# Sheet1.net
KiCad netlist of a schematic drawn in Altium Designer
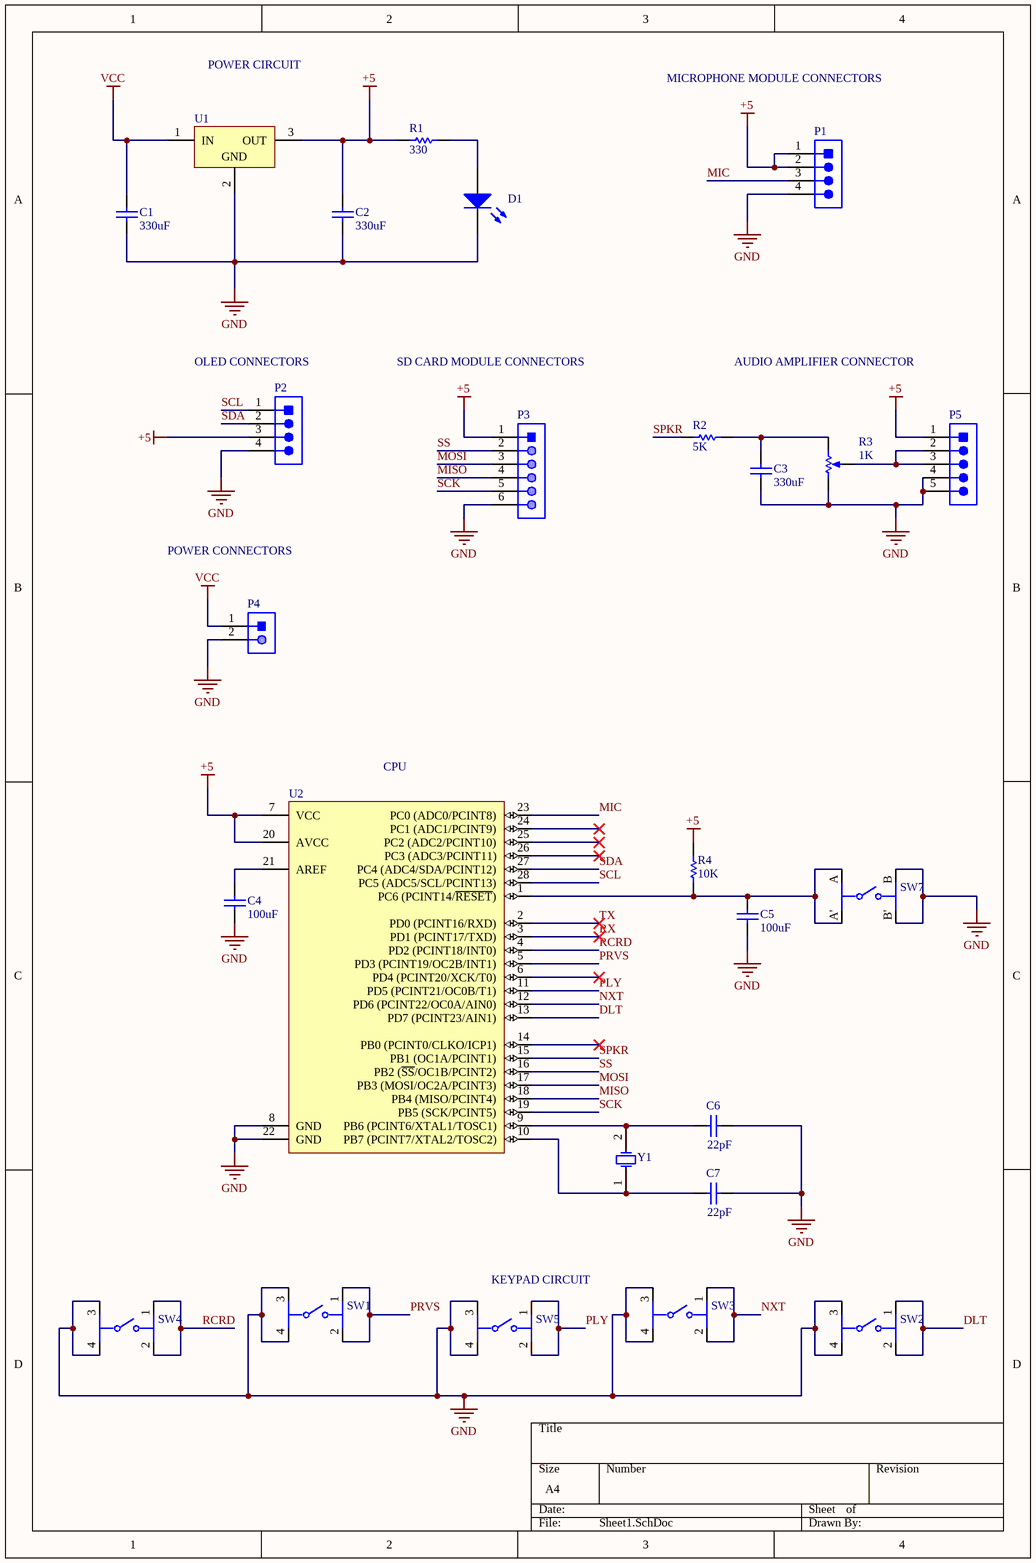
[diagram p0: Sheet1.SchDoc]

(export (version "E")
  (design (tool "Eeschema 10.0.6"))
  (components
    (comp (ref "C1")
      (value "330uF")
      (footprint "RAD-0.3")
      (description "Capacitor")
      (fields (field (name "PUBLISHER") "Altium Limited"))
      (libsource (lib "Miscellaneous Devices") (part "Cap"))
    )
    (comp (ref "C2")
      (value "330uF")
      (footprint "RAD-0.3")
      (description "Capacitor")
      (fields (field (name "PUBLISHER") "Altium Limited"))
      (libsource (lib "Miscellaneous Devices") (part "Cap"))
    )
    (comp (ref "C3")
      (value "330uF")
      (footprint "RAD-0.3")
      (description "Capacitor")
      (fields (field (name "PUBLISHER") "Altium Limited"))
      (libsource (lib "Miscellaneous Devices") (part "Cap"))
    )
    (comp (ref "C4")
      (value "~")
      (footprint "KEMT-C330C105M5U5TA")
      (description "Ceramic Capacitor, 1 uF, +/- 20%, 50 V, -10 to 85 degC, 2-Pin THD, RoHS, Bulk")
      (fields
        (field (name "TOLERANCE") "±20%")
        (field (name "CAPACITANCE") "100uF")
        (field (name "MANUFACTURER") "Kemet")
      )
      (libsource (lib "Altium Content Vault") (part "CAP-NP-2"))
    )
    (comp (ref "C5")
      (value "C330C105M5U5TA")
      (footprint "KEMT-C330C105M5U5TA")
      (description "Ceramic Capacitor, 1 uF, +/- 20%, 50 V, -10 to 85 degC, 2-Pin THD, RoHS, Bulk")
      (fields
        (field (name "TOLERANCE") "±20%")
        (field (name "CAPACITANCE") "100uF")
        (field (name "MANUFACTURER") "Kemet")
      )
      (libsource (lib "Altium Content Vault") (part "CAP-NP-2"))
    )
    (comp (ref "C6")
      (value "C330C105M5U5TA")
      (footprint "KEMT-C330C105M5U5TA")
      (description "Ceramic Capacitor, 1 uF, +/- 20%, 50 V, -10 to 85 degC, 2-Pin THD, RoHS, Bulk")
      (fields
        (field (name "TOLERANCE") "±20%")
        (field (name "CAPACITANCE") "22pF")
        (field (name "MANUFACTURER") "Kemet")
      )
      (libsource (lib "Altium Content Vault") (part "CAP-NP-2"))
    )
    (comp (ref "C7")
      (value "C330C105M5U5TA")
      (footprint "KEMT-C330C105M5U5TA")
      (description "Ceramic Capacitor, 1 uF, +/- 20%, 50 V, -10 to 85 degC, 2-Pin THD, RoHS, Bulk")
      (fields
        (field (name "TOLERANCE") "±20%")
        (field (name "CAPACITANCE") "22pF")
        (field (name "MANUFACTURER") "Kemet")
      )
      (libsource (lib "Altium Content Vault") (part "CAP-NP-2"))
    )
    (comp (ref "D1")
      (value "LED1")
      (footprint "LED-1")
      (description "Typical RED GaAs LED")
      (fields (field (name "PUBLISHER") "Altium Limited"))
      (libsource (lib "Miscellaneous Devices") (part "LED1"))
    )
    (comp (ref "P1")
      (value "640456-4")
      (footprint "TECO-640456-4")
      (description "Male Header, Pitch 2.54 mm, 1 x 4 Position, Height 10.03 mm, Tail Length 3.56 mm, RoHS, Bulk")
      (fields (field (name "MANUFACTURER") "TE Connectivity"))
      (libsource (lib "Altium Content Vault") (part "CN-1P-M-R4"))
    )
    (comp (ref "P2")
      (value "640456-4")
      (footprint "TECO-640456-4")
      (description "Male Header, Pitch 2.54 mm, 1 x 4 Position, Height 10.03 mm, Tail Length 3.56 mm, RoHS, Bulk")
      (fields (field (name "MANUFACTURER") "TE Connectivity"))
      (libsource (lib "Altium Content Vault") (part "CN-1P-M-R4"))
    )
    (comp (ref "P3")
      (value "66200611122")
      (footprint "66200611122")
      (description "THT Male Header WR-MPC3, Vertical, Single Row, pitch 3 mm, 6 pins")
      (fields (field (name "MANUFACTURER") "Wurth Elektronik") (field (name "PUBLISHER") "WurthElektronik"))
      (libsource (lib "Altium Content Vault") (part "WE-CN-1P-M-R6"))
    )
    (comp (ref "P4")
      (value "61900211121")
      (footprint "61900211121")
      (description "Male Locking Header WR-WTB, THT, Vertical, pitch 2.54 mm, 1 x 2 position")
      (fields (field (name "MANUFACTURER") "Wurth Elektronik") (field (name "PUBLISHER") "WurthElektronik"))
      (libsource (lib "Altium Content Vault") (part "WE-CN-1P-M-R2"))
    )
    (comp (ref "P5")
      (value "640456-5")
      (footprint "TECO-640456-5")
      (fields (field (name "MANUFACTURER") "TE Connectivity"))
      (libsource (lib "Altium Content Vault") (part "CN-1P-M-R5"))
    )
    (comp (ref "R1")
      (value "330")
      (footprint "AXIAL-0.3")
      (description "Resistor")
      (fields (field (name "PUBLISHER") "Altium Limited"))
      (libsource (lib "Miscellaneous Devices") (part "Res1"))
    )
    (comp (ref "R2")
      (value "5K")
      (footprint "AXIAL-0.3")
      (description "Resistor")
      (fields (field (name "PUBLISHER") "Altium Limited"))
      (libsource (lib "Miscellaneous Devices") (part "Res1"))
    )
    (comp (ref "R3")
      (value "1K")
      (footprint "VR5")
      (description "Potentiometer")
      (fields (field (name "PUBLISHER") "Altium Limited"))
      (libsource (lib "Miscellaneous Devices") (part "RPot"))
    )
    (comp (ref "R4")
      (value "10K")
      (footprint "AXIAL-0.3")
      (description "Resistor")
      (fields (field (name "PUBLISHER") "Altium Limited"))
      (libsource (lib "Miscellaneous Devices") (part "Res1"))
    )
    (comp (ref "SW1")
      (value "FSM100")
      (footprint "FP-FSM100-MFG")
      (description "SWITCH TACTILE SPST-NO 0.05A 24V")
      (libsource (lib "Altium Content Vault") (part "1adf0dd01260c80cf25a44bfd6b99ba"))
    )
    (comp (ref "SW2")
      (value "FSM100")
      (footprint "FP-FSM100-MFG")
      (description "SWITCH TACTILE SPST-NO 0.05A 24V")
      (libsource (lib "Altium Content Vault") (part "1adf0dd01260c80cf25a44bfd6b99ba"))
    )
    (comp (ref "SW3")
      (value "FSM100")
      (footprint "FP-FSM100-MFG")
      (description "SWITCH TACTILE SPST-NO 0.05A 24V")
      (libsource (lib "Altium Content Vault") (part "1adf0dd01260c80cf25a44bfd6b99ba"))
    )
    (comp (ref "SW4")
      (value "FSM100")
      (footprint "FP-FSM100-MFG")
      (description "SWITCH TACTILE SPST-NO 0.05A 24V")
      (libsource (lib "Altium Content Vault") (part "1adf0dd01260c80cf25a44bfd6b99ba"))
    )
    (comp (ref "SW5")
      (value "FSM100")
      (footprint "FP-FSM100-MFG")
      (description "SWITCH TACTILE SPST-NO 0.05A 24V")
      (libsource (lib "Altium Content Vault") (part "1adf0dd01260c80cf25a44bfd6b99ba"))
    )
    (comp (ref "SW7")
      (value "EVQ-PAG07K")
      (footprint "FP-EVQ-PAG07K-MFG")
      (description "SWITCH TACTILE SPST-NO 0.02A 15V")
      (libsource (lib "Altium Content Vault") (part "75038bc65b1af1a6bd057da08483287"))
    )
    (comp (ref "U1")
      (value "L7805CV")
      (footprint "TO220")
      (description "Positive Voltage Regulator, 5V, 3-Pin TO-220")
      (libsource (lib "Altium Content Vault") (part "PM-REG-L4940-SIL3"))
    )
    (comp (ref "U2")
      (value "ATmega328P-PU")
      (footprint "28P3")
      (libsource (lib "Altium Content Vault") (part "MC-8B-ATM48-IL28"))
    )
    (comp (ref "Y1")
      (value "XTAL")
      (footprint "R38")
      (description "Crystal Oscillator")
      (fields (field (name "PUBLISHER") "Altium Limited"))
      (libsource (lib "Miscellaneous Devices") (part "XTAL"))
    )
  )
  (nets
    (net (code "1") (name "+5") (class "Default")
      (node (ref "C2") (pin "2") (pinfunction "2_2") (pintype "passive"))
      (node (ref "P1") (pin "1") (pinfunction "1_1") (pintype "passive"))
      (node (ref "P1") (pin "2") (pinfunction "2_2") (pintype "passive"))
      (node (ref "P2") (pin "3") (pinfunction "3_3") (pintype "passive"))
      (node (ref "P3") (pin "1") (pinfunction "1_1") (pintype "passive"))
      (node (ref "P5") (pin "1") (pinfunction "DTR_1") (pintype "passive"))
      (node (ref "R1") (pin "1") (pinfunction "1_1") (pintype "passive"))
      (node (ref "R4") (pin "1") (pinfunction "1_1") (pintype "passive"))
      (node (ref "U1") (pin "3") (pinfunction "OUT_3") (pintype "power_in"))
      (node (ref "U2") (pin "20") (pinfunction "AVCC_20") (pintype "power_in"))
      (node (ref "U2") (pin "7") (pinfunction "VCC_7") (pintype "power_in"))
    )
    (net (code "2") (name "/DLT") (class "Default")
      (node (ref "SW2") (pin "1") (pinfunction "1_1") (pintype "passive"))
      (node (ref "SW2") (pin "2") (pinfunction "2_2") (pintype "passive"))
      (node (ref "U2") (pin "13") (pinfunction "PD7_(PCINT23/AIN1)_13") (pintype "bidirectional"))
    )
    (net (code "3") (name "/MIC") (class "Default")
      (node (ref "P1") (pin "3") (pinfunction "3_3") (pintype "passive"))
      (node (ref "U2") (pin "23") (pinfunction "PC0_(ADC0/PCINT8)_23") (pintype "bidirectional"))
    )
    (net (code "4") (name "/MISO") (class "Default")
      (node (ref "P3") (pin "4") (pinfunction "4_4") (pintype "passive"))
      (node (ref "U2") (pin "18") (pinfunction "PB4_(MISO/PCINT4)_18") (pintype "bidirectional"))
    )
    (net (code "5") (name "/MOSI") (class "Default")
      (node (ref "P3") (pin "3") (pinfunction "3_3") (pintype "passive"))
      (node (ref "U2") (pin "17") (pinfunction "PB3_(MOSI/OC2A/PCINT3)_17") (pintype "bidirectional"))
    )
    (net (code "6") (name "/NXT") (class "Default")
      (node (ref "SW3") (pin "1") (pinfunction "1_1") (pintype "passive"))
      (node (ref "SW3") (pin "2") (pinfunction "2_2") (pintype "passive"))
      (node (ref "U2") (pin "12") (pinfunction "PD6_(PCINT22/OC0A/AIN0)_12") (pintype "bidirectional"))
    )
    (net (code "7") (name "/PLY") (class "Default")
      (node (ref "SW5") (pin "1") (pinfunction "1_1") (pintype "passive"))
      (node (ref "SW5") (pin "2") (pinfunction "2_2") (pintype "passive"))
      (node (ref "U2") (pin "11") (pinfunction "PD5_(PCINT21/OC0B/T1)_11") (pintype "bidirectional"))
    )
    (net (code "8") (name "/PRVS") (class "Default")
      (node (ref "SW1") (pin "1") (pinfunction "1_1") (pintype "passive"))
      (node (ref "SW1") (pin "2") (pinfunction "2_2") (pintype "passive"))
      (node (ref "U2") (pin "5") (pinfunction "PD3_(PCINT19/OC2B/INT1)_5") (pintype "bidirectional"))
    )
    (net (code "9") (name "/RCRD") (class "Default")
      (node (ref "SW4") (pin "1") (pinfunction "1_1") (pintype "passive"))
      (node (ref "SW4") (pin "2") (pinfunction "2_2") (pintype "passive"))
      (node (ref "U2") (pin "4") (pinfunction "PD2_(PCINT18/INT0)_4") (pintype "bidirectional"))
    )
    (net (code "10") (name "/RX") (class "Default")
      (node (ref "U2") (pin "3") (pinfunction "PD1_(PCINT17/TXD)_3") (pintype "bidirectional+no_connect"))
    )
    (net (code "11") (name "/SCK") (class "Default")
      (node (ref "P3") (pin "5") (pinfunction "5_5") (pintype "passive"))
      (node (ref "U2") (pin "19") (pinfunction "PB5_(SCK/PCINT5)_19") (pintype "bidirectional"))
    )
    (net (code "12") (name "/SCL") (class "Default")
      (node (ref "P2") (pin "1") (pinfunction "1_1") (pintype "passive"))
      (node (ref "U2") (pin "28") (pinfunction "PC5_(ADC5/SCL/PCINT13)_28") (pintype "bidirectional"))
    )
    (net (code "13") (name "/SDA") (class "Default")
      (node (ref "P2") (pin "2") (pinfunction "2_2") (pintype "passive"))
      (node (ref "U2") (pin "27") (pinfunction "PC4_(ADC4/SDA/PCINT12)_27") (pintype "bidirectional"))
    )
    (net (code "14") (name "/SPKR") (class "Default")
      (node (ref "R2") (pin "2") (pinfunction "2_2") (pintype "passive"))
      (node (ref "U2") (pin "15") (pinfunction "PB1_(OC1A/PCINT1)_15") (pintype "bidirectional"))
    )
    (net (code "15") (name "/SS") (class "Default")
      (node (ref "P3") (pin "2") (pinfunction "2_2") (pintype "passive"))
      (node (ref "U2") (pin "16") (pinfunction "PB2_(~{SS}/OC1B/PCINT2)_16") (pintype "bidirectional"))
    )
    (net (code "16") (name "/TX") (class "Default")
      (node (ref "U2") (pin "2") (pinfunction "PD0_(PCINT16/RXD)_2") (pintype "bidirectional+no_connect"))
    )
    (net (code "17") (name "GND") (class "Default")
      (node (ref "C1") (pin "1") (pinfunction "1_1") (pintype "passive"))
      (node (ref "C2") (pin "1") (pinfunction "1_1") (pintype "passive"))
      (node (ref "C3") (pin "1") (pinfunction "1_1") (pintype "passive"))
      (node (ref "C4") (pin "1") (pinfunction "1_1") (pintype "passive"))
      (node (ref "C5") (pin "1") (pinfunction "1_1") (pintype "passive"))
      (node (ref "C6") (pin "2") (pinfunction "2_2") (pintype "passive"))
      (node (ref "C7") (pin "2") (pinfunction "2_2") (pintype "passive"))
      (node (ref "D1") (pin "2") (pinfunction "K_2") (pintype "passive"))
      (node (ref "P1") (pin "4") (pinfunction "4_4") (pintype "passive"))
      (node (ref "P2") (pin "4") (pinfunction "4_4") (pintype "passive"))
      (node (ref "P3") (pin "6") (pinfunction "6_6") (pintype "passive"))
      (node (ref "P4") (pin "2") (pinfunction "2_2") (pintype "passive"))
      (node (ref "P5") (pin "4") (pinfunction "VCC_4") (pintype "passive"))
      (node (ref "P5") (pin "5") (pinfunction "CTS_5") (pintype "passive"))
      (node (ref "R3") (pin "1") (pinfunction "TOP_1") (pintype "passive"))
      (node (ref "SW1") (pin "3") (pinfunction "3_3") (pintype "passive"))
      (node (ref "SW1") (pin "4") (pinfunction "4_4") (pintype "passive"))
      (node (ref "SW2") (pin "3") (pinfunction "3_3") (pintype "passive"))
      (node (ref "SW2") (pin "4") (pinfunction "4_4") (pintype "passive"))
      (node (ref "SW3") (pin "3") (pinfunction "3_3") (pintype "passive"))
      (node (ref "SW3") (pin "4") (pinfunction "4_4") (pintype "passive"))
      (node (ref "SW4") (pin "3") (pinfunction "3_3") (pintype "passive"))
      (node (ref "SW4") (pin "4") (pinfunction "4_4") (pintype "passive"))
      (node (ref "SW5") (pin "3") (pinfunction "3_3") (pintype "passive"))
      (node (ref "SW5") (pin "4") (pinfunction "4_4") (pintype "passive"))
      (node (ref "SW7") (pin "B") (pinfunction "B_B") (pintype "passive"))
      (node (ref "SW7") (pin "B'") (pinfunction "B'_B'") (pintype "passive"))
      (node (ref "U1") (pin "2") (pinfunction "GND_2") (pintype "power_in"))
      (node (ref "U2") (pin "22") (pinfunction "GND_22") (pintype "power_in"))
      (node (ref "U2") (pin "8") (pinfunction "GND_8") (pintype "power_in"))
    )
    (net (code "18") (name "Net-(D1-A)") (class "Default")
      (node (ref "D1") (pin "1") (pinfunction "A_1") (pintype "passive"))
      (node (ref "R1") (pin "2") (pinfunction "2_2") (pintype "passive"))
    )
    (net (code "19") (name "Net-(P5-RXI)") (class "Default")
      (node (ref "P5") (pin "2") (pinfunction "RXI_2") (pintype "passive"))
      (node (ref "P5") (pin "3") (pinfunction "TXO_3") (pintype "passive"))
      (node (ref "R3") (pin "3") (pinfunction "TAP_3") (pintype "passive"))
    )
    (net (code "20") (name "Net-(R3-BOT)") (class "Default")
      (node (ref "C3") (pin "2") (pinfunction "2_2") (pintype "passive"))
      (node (ref "R2") (pin "1") (pinfunction "1_1") (pintype "passive"))
      (node (ref "R3") (pin "2") (pinfunction "BOT_2") (pintype "passive"))
    )
    (net (code "21") (name "Net-(U2-AREF)") (class "Default")
      (node (ref "C4") (pin "2") (pinfunction "2_2") (pintype "passive"))
      (node (ref "U2") (pin "21") (pinfunction "AREF_21") (pintype "power_in"))
    )
    (net (code "22") (name "Net-(U2-PB6_(PCINT6{slash}XTAL1{slash}TOSC1))") (class "Default")
      (node (ref "C6") (pin "1") (pinfunction "1_1") (pintype "passive"))
      (node (ref "U2") (pin "9") (pinfunction "PB6_(PCINT6/XTAL1/TOSC1)_9") (pintype "bidirectional"))
      (node (ref "Y1") (pin "2") (pinfunction "OSC2_2") (pintype "passive"))
    )
    (net (code "23") (name "Net-(U2-PB7_(PCINT7{slash}XTAL2{slash}TOSC2))") (class "Default")
      (node (ref "C7") (pin "1") (pinfunction "1_1") (pintype "passive"))
      (node (ref "U2") (pin "10") (pinfunction "PB7_(PCINT7/XTAL2/TOSC2)_10") (pintype "bidirectional"))
      (node (ref "Y1") (pin "1") (pinfunction "OSC1_1") (pintype "passive"))
    )
    (net (code "24") (name "Net-(U2-PC6_(PCINT14{slash}~{RESET}))") (class "Default")
      (node (ref "C5") (pin "2") (pinfunction "2_2") (pintype "passive"))
      (node (ref "R4") (pin "2") (pinfunction "2_2") (pintype "passive"))
      (node (ref "SW7") (pin "A") (pinfunction "A_A") (pintype "passive"))
      (node (ref "SW7") (pin "A'") (pinfunction "A'_A'") (pintype "passive"))
      (node (ref "U2") (pin "1") (pinfunction "PC6_(PCINT14/~{RESET})_1") (pintype "bidirectional"))
    )
    (net (code "25") (name "VCC") (class "Default")
      (node (ref "C1") (pin "2") (pinfunction "2_2") (pintype "passive"))
      (node (ref "P4") (pin "1") (pinfunction "1_1") (pintype "passive"))
      (node (ref "U1") (pin "1") (pinfunction "IN_1") (pintype "power_in"))
    )
    (net (code "26") (name "unconnected-(U2-PB0_(PCINT0{slash}CLKO{slash}ICP1)-Pad14)") (class "Default")
      (node (ref "U2") (pin "14") (pinfunction "PB0_(PCINT0/CLKO/ICP1)_14") (pintype "bidirectional+no_connect"))
    )
    (net (code "27") (name "unconnected-(U2-PC1_(ADC1{slash}PCINT9)-Pad24)") (class "Default")
      (node (ref "U2") (pin "24") (pinfunction "PC1_(ADC1/PCINT9)_24") (pintype "bidirectional+no_connect"))
    )
    (net (code "28") (name "unconnected-(U2-PC2_(ADC2{slash}PCINT10)-Pad25)") (class "Default")
      (node (ref "U2") (pin "25") (pinfunction "PC2_(ADC2/PCINT10)_25") (pintype "bidirectional+no_connect"))
    )
    (net (code "29") (name "unconnected-(U2-PC3_(ADC3{slash}PCINT11)-Pad26)") (class "Default")
      (node (ref "U2") (pin "26") (pinfunction "PC3_(ADC3/PCINT11)_26") (pintype "bidirectional+no_connect"))
    )
    (net (code "30") (name "unconnected-(U2-PD4_(PCINT20{slash}XCK{slash}T0)-Pad6)") (class "Default")
      (node (ref "U2") (pin "6") (pinfunction "PD4_(PCINT20/XCK/T0)_6") (pintype "bidirectional+no_connect"))
    )
  )
)
